# diapers.net
KiCad netlist of a schematic drawn in Altium Designer
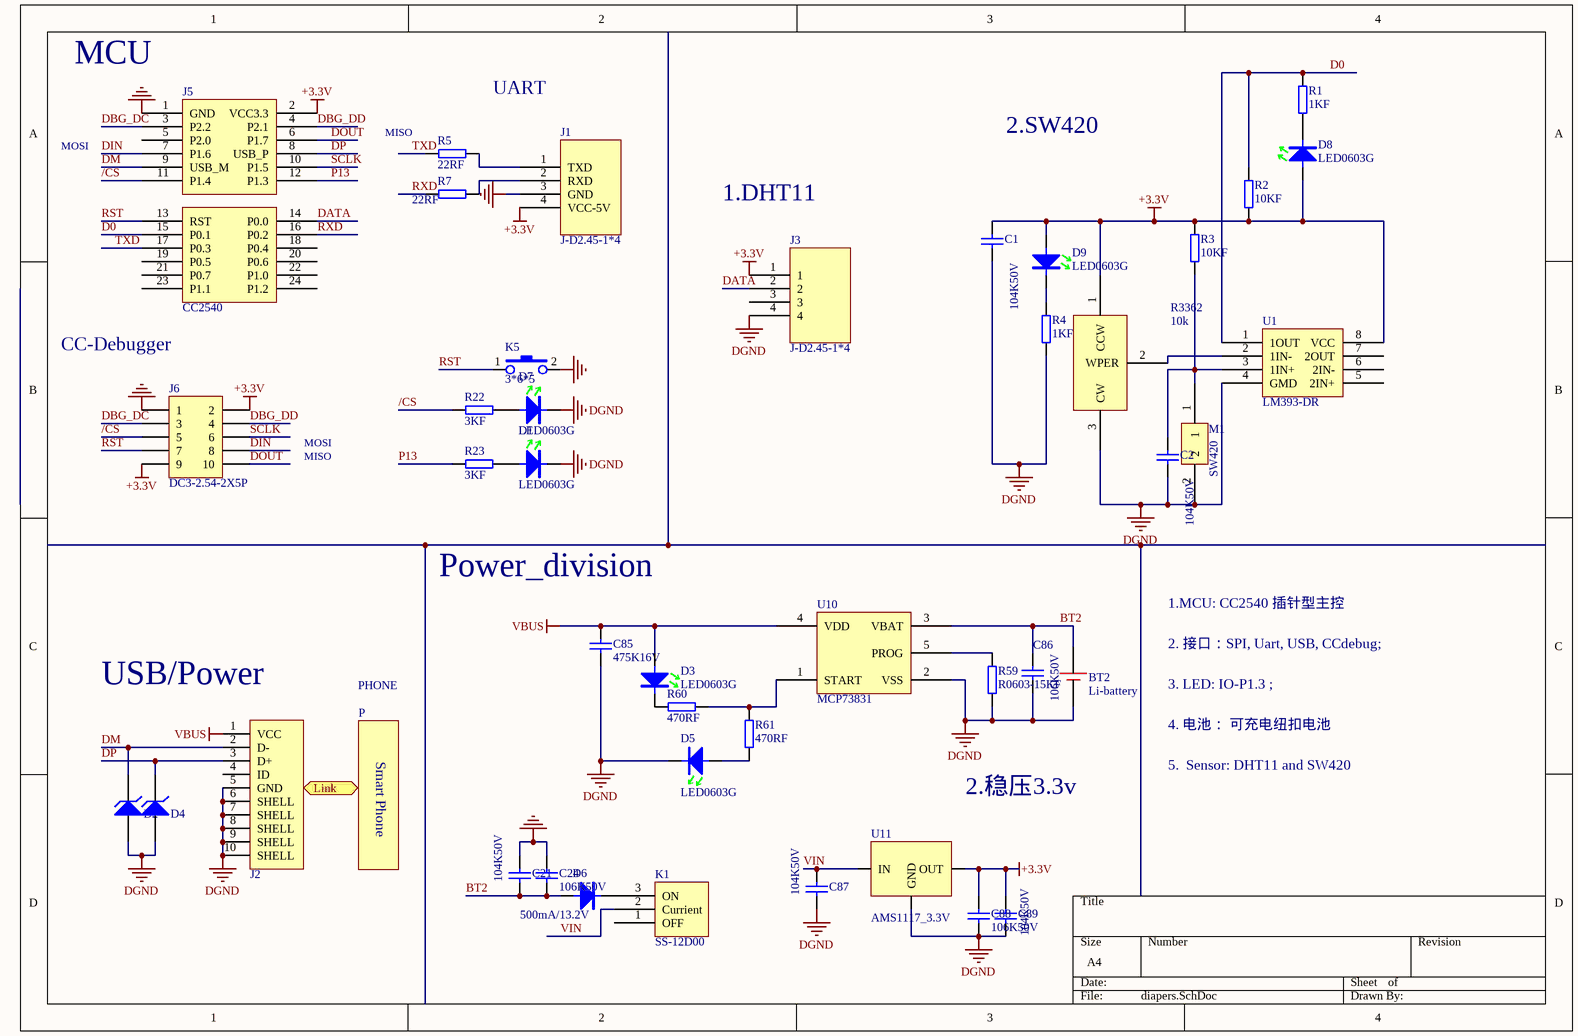
[diagram p0: diapers.SchDoc]

(export (version "E")
  (design (tool "Eeschema 10.0.6"))
  (components
    (comp (ref "BT2")
      (value "Li-battery")
      (footprint "LIR2032")
      (description "纽扣电池LIR2023")
      (libsource (lib "Others") (part "Li-batttery"))
    )
    (comp (ref "C1")
      (value "104K50V")
      (footprint "C0603")
      (description "贴片电容-陶瓷")
      (libsource (lib "Capacitor") (part "C0603X7R-104K50V"))
    )
    (comp (ref "C2")
      (value "104K50V")
      (footprint "C0603")
      (description "贴片电容-陶瓷")
      (libsource (lib "Capacitor") (part "C0603X7R-104K50V"))
    )
    (comp (ref "C21")
      (value "104K50V")
      (footprint "C0603")
      (description "贴片电容-陶瓷")
      (libsource (lib "Capacitor") (part "C0603X7R-104K50V"))
    )
    (comp (ref "C24")
      (value "106K50V")
      (footprint "C0603")
      (description "贴片电容-陶瓷")
      (libsource (lib "Capacitor") (part "C0603X7R-106K50V"))
    )
    (comp (ref "C85")
      (value "475K16V")
      (footprint "C0603")
      (description "贴片电容-陶瓷")
      (libsource (lib "Capacitor") (part "C0603X7R-475K16V"))
    )
    (comp (ref "C86")
      (value "106K50V")
      (footprint "C0603")
      (description "贴片电容-陶瓷")
      (libsource (lib "Capacitor") (part "C0603X7R-106K50V"))
    )
    (comp (ref "C87")
      (value "104K50V")
      (footprint "C0603")
      (description "贴片电容-陶瓷")
      (libsource (lib "Capacitor") (part "C0603X7R-104K50V"))
    )
    (comp (ref "C88")
      (value "106K50V")
      (footprint "C0603")
      (description "贴片电容-陶瓷")
      (libsource (lib "Capacitor") (part "C0603X7R-106K50V"))
    )
    (comp (ref "C89")
      (value "104K50V")
      (footprint "C0603")
      (description "贴片电容-陶瓷")
      (libsource (lib "Capacitor") (part "C0603X7R-104K50V"))
    )
    (comp (ref "D1")
      (value "LED0603G")
      (footprint "D-LED0603G")
      (description "贴片二极管-LED")
      (libsource (lib "aiwacV2.0") (part "DLED-0603-G"))
    )
    (comp (ref "D2")
      (value "ESDA_TR1/0603")
      (footprint "HS_0603D")
      (description "Zener Diode")
      (fields (field (name "PUBLISHER") "*"))
      (libsource (lib "aiwacV2.0") (part "D Zener"))
    )
    (comp (ref "D3")
      (value "LED0603G")
      (footprint "D-LED0603G")
      (description "贴片二极管-LED")
      (libsource (lib "Diode") (part "DLED-0603-G"))
    )
    (comp (ref "D4")
      (value "ESDA_TR1/0603")
      (footprint "HS_0603D")
      (description "Zener Diode")
      (fields (field (name "PUBLISHER") "*"))
      (libsource (lib "aiwacV2.0") (part "D Zener"))
    )
    (comp (ref "D5")
      (value "LED0603G")
      (footprint "D-LED0603G")
      (description "贴片二极管-LED")
      (libsource (lib "Diode") (part "DLED-0603-G"))
    )
    (comp (ref "D6")
      (value "500mA/13.2V")
      (footprint "D1206")
      (description "500mA/13.2V 自恢复保险丝")
      (libsource (lib "Diode") (part "1206MSD"))
    )
    (comp (ref "D7")
      (value "LED0603G")
      (footprint "D-LED0603G")
      (description "贴片二极管-LED")
      (libsource (lib "aiwacV2.0") (part "DLED-0603-G"))
    )
    (comp (ref "D8")
      (value "LED0603G")
      (footprint "D-LED0603G")
      (description "贴片二极管-LED")
      (libsource (lib "Diode") (part "DLED-0603-G"))
    )
    (comp (ref "D9")
      (value "LED0603G")
      (footprint "D-LED0603G")
      (description "贴片二极管-LED")
      (libsource (lib "Diode") (part "DLED-0603-G"))
    )
    (comp (ref "J1")
      (value "J-D2.45-1*4")
      (footprint "D2.54-1*4P")
      (libsource (lib "Connector") (part "J-D2.54-1*4单排排母"))
    )
    (comp (ref "J2")
      (value "USB-MINI-SOCKET")
      (footprint "MICRO-USB - 5.9")
      (description "USB-A卧式插座")
      (libsource (lib "epic2") (part "J-USB-MINI-SOCKET"))
    )
    (comp (ref "J3")
      (value "J-D2.45-1*4")
      (footprint "D2.54-1*4P")
      (libsource (lib "Connector") (part "J-D2.54-1*4单排排母"))
    )
    (comp (ref "J5")
      (value "CC2540")
      (footprint "PCBComponent_1")
      (description "蓝牙主控模块的接口")
      (libsource (lib "Module") (part "CC2540"))
    )
    (comp (ref "J6")
      (value "DC3-2.54-2X5P")
      (footprint "DC3-2.54-2X5P")
      (description "简牛插座-直针")
      (libsource (lib "Connector") (part "J-DC3-2.54-2X5P"))
    )
    (comp (ref "K1")
      (value "SS-12D00")
      (footprint "SS-12D00")
      (libsource (lib "Key") (part "SS-12D00(1P2T) 立式 柄高5MM"))
    )
    (comp (ref "K5")
      (value "3*6*5")
      (footprint "S-K3*6")
      (description "贴片-卧式轻触开关")
      (libsource (lib "Key") (part "3*6*5"))
    )
    (comp (ref "M1")
      (value "SW420")
      (footprint "SW420")
      (description "长闭震动开关")
      (libsource (lib "Module") (part "SW420"))
    )
    (comp (ref "P") (value "PHONE") (libsource (lib "epic") (part "PHONE")))
    (comp (ref "R1")
      (value "1KF")
      (footprint "R0603")
      (description "贴片电阻-通用")
      (libsource (lib "Resistor") (part "R0603-1KF"))
    )
    (comp (ref "R2")
      (value "10KF")
      (footprint "R0603")
      (description "贴片电阻-通用")
      (libsource (lib "Resistor") (part "R0603-10KF"))
    )
    (comp (ref "R3")
      (value "10KF")
      (footprint "R0603")
      (description "贴片电阻-通用")
      (libsource (lib "Resistor") (part "R0603-10KF"))
    )
    (comp (ref "R4")
      (value "1KF")
      (footprint "R0603")
      (description "贴片电阻-通用")
      (libsource (lib "Resistor") (part "R0603-1KF"))
    )
    (comp (ref "R5")
      (value "22RF")
      (footprint "R0603")
      (description "贴片电阻-通用")
      (libsource (lib "Resistor") (part "R0603-22RF"))
    )
    (comp (ref "R7")
      (value "22RF")
      (footprint "R0603")
      (description "贴片电阻-通用")
      (libsource (lib "Resistor") (part "R0603-22RF"))
    )
    (comp (ref "R22")
      (value "3KF")
      (footprint "R0603")
      (description "贴片电阻-通用")
      (libsource (lib "Resistor") (part "R0603-3KF"))
    )
    (comp (ref "R23")
      (value "3KF")
      (footprint "R0603")
      (description "贴片电阻-通用")
      (libsource (lib "Resistor") (part "R0603-3KF"))
    )
    (comp (ref "R59")
      (value "R0603-15KF")
      (footprint "R0603")
      (description "贴片电容-通用")
      (libsource (lib "Resistor") (part "R0603-15KF"))
    )
    (comp (ref "R60")
      (value "470RF")
      (footprint "R0603")
      (description "贴片电阻-通用")
      (libsource (lib "Resistor") (part "R0603-470RF"))
    )
    (comp (ref "R61")
      (value "470RF")
      (footprint "R0603")
      (description "贴片电阻-通用")
      (libsource (lib "Resistor") (part "R0603-470RF"))
    )
    (comp (ref "R3362")
      (value "10k")
      (footprint "R3326P")
      (description "电位器精密可调电阻")
      (libsource (lib "Resistor") (part "R3362-10K"))
    )
    (comp (ref "U1")
      (value "LM393-DR")
      (footprint "LM393")
      (description "双路比较器")
      (libsource (lib "IC") (part "LM393-DR"))
    )
    (comp (ref "U10")
      (value "MCP73831")
      (footprint "SOT23-5N")
      (description "charge IC")
      (libsource (lib "IC") (part "MCP73831"))
    )
    (comp (ref "U11")
      (value "AMS1117_3.3V")
      (footprint "SOT-223")
      (libsource (lib "IC") (part "AMS1117-3.3V"))
    )
  )
  (nets
    (net (code "1") (name "+3.3V") (class "Default")
      (node (ref "C1") (pin "1") (pinfunction "1_1") (pintype "passive"))
      (node (ref "C88") (pin "2") (pinfunction "2_2") (pintype "passive"))
      (node (ref "C89") (pin "1") (pinfunction "1_1") (pintype "passive"))
      (node (ref "D8") (pin "1") (pinfunction "1_1") (pintype "passive"))
      (node (ref "D9") (pin "1") (pinfunction "1_1") (pintype "passive"))
      (node (ref "J1") (pin "4") (pinfunction "VCC-5V_4") (pintype "passive"))
      (node (ref "J3") (pin "1") (pinfunction "TXD_1") (pintype "passive"))
      (node (ref "J5") (pin "2") (pinfunction "VCC3.3_2") (pintype "passive"))
      (node (ref "J6") (pin "2") (pinfunction "2_2") (pintype "passive"))
      (node (ref "J6") (pin "9") (pinfunction "9_9") (pintype "passive"))
      (node (ref "R2") (pin "1") (pinfunction "1_1") (pintype "passive"))
      (node (ref "R3") (pin "2") (pinfunction "2_2") (pintype "passive"))
      (node (ref "R3362") (pin "1") (pinfunction "CCW_1") (pintype "passive"))
      (node (ref "U1") (pin "8") (pinfunction "VCC_8") (pintype "passive"))
      (node (ref "U11") (pin "2") (pinfunction "OUT_2") (pintype "passive"))
    )
    (net (code "2") (name "/BT2") (class "Default")
      (node (ref "BT2") (pin "1") (pinfunction "1_1") (pintype "passive"))
      (node (ref "C21") (pin "2") (pinfunction "2_2") (pintype "passive"))
      (node (ref "C24") (pin "1") (pinfunction "1_1") (pintype "passive"))
      (node (ref "C86") (pin "1") (pinfunction "1_1") (pintype "passive"))
      (node (ref "D6") (pin "1") (pinfunction "1_1") (pintype "passive"))
      (node (ref "U10") (pin "3") (pinfunction "VBAT_3") (pintype "passive"))
    )
    (net (code "3") (name "/D0") (class "Default")
      (node (ref "J5") (pin "15") (pinfunction "P0.1_15") (pintype "passive"))
      (node (ref "R1") (pin "1") (pinfunction "1_1") (pintype "passive"))
      (node (ref "R2") (pin "2") (pinfunction "2_2") (pintype "passive"))
      (node (ref "U1") (pin "1") (pinfunction "1OUT_1") (pintype "passive"))
    )
    (net (code "4") (name "/DATA") (class "Default")
      (node (ref "J3") (pin "2") (pinfunction "RXD_2") (pintype "passive"))
      (node (ref "J5") (pin "14") (pinfunction "P0.0_14") (pintype "passive"))
    )
    (net (code "5") (name "/DBG_DC") (class "Default")
      (node (ref "J5") (pin "3") (pinfunction "P2.2_3") (pintype "passive"))
      (node (ref "J6") (pin "3") (pinfunction "3_3") (pintype "passive"))
    )
    (net (code "6") (name "/DBG_DD") (class "Default")
      (node (ref "J5") (pin "4") (pinfunction "P2.1_4") (pintype "passive"))
      (node (ref "J6") (pin "4") (pinfunction "4_4") (pintype "passive"))
    )
    (net (code "7") (name "/DIN") (class "Default")
      (node (ref "J5") (pin "7") (pinfunction "P1.6_7") (pintype "passive"))
      (node (ref "J6") (pin "8") (pinfunction "8_8") (pintype "passive"))
    )
    (net (code "8") (name "/DM") (class "Default")
      (node (ref "D2") (pin "2") (pinfunction "K_2") (pintype "passive"))
      (node (ref "J2") (pin "2") (pinfunction "D-_2") (pintype "passive"))
      (node (ref "J5") (pin "9") (pinfunction "USB_M_9") (pintype "passive"))
    )
    (net (code "9") (name "/DOUT") (class "Default")
      (node (ref "J5") (pin "6") (pinfunction "P1.7_6") (pintype "passive"))
      (node (ref "J6") (pin "10") (pinfunction "10_10") (pintype "passive"))
    )
    (net (code "10") (name "/DP") (class "Default")
      (node (ref "D4") (pin "2") (pinfunction "K_2") (pintype "passive"))
      (node (ref "J2") (pin "3") (pinfunction "D+_3") (pintype "passive"))
      (node (ref "J5") (pin "8") (pinfunction "USB_P_8") (pintype "passive"))
    )
    (net (code "12") (name "/P13") (class "Default")
      (node (ref "J5") (pin "12") (pinfunction "P1.3_12") (pintype "passive"))
      (node (ref "R23") (pin "1") (pinfunction "1_1") (pintype "passive"))
    )
    (net (code "13") (name "/RST") (class "Default")
      (node (ref "J5") (pin "13") (pinfunction "RST_13") (pintype "passive"))
      (node (ref "J6") (pin "7") (pinfunction "7_7") (pintype "passive"))
      (node (ref "K5") (pin "1") (pinfunction "1_1") (pintype "passive"))
    )
    (net (code "14") (name "/RXD") (class "Default")
      (node (ref "J5") (pin "16") (pinfunction "P0.2_16") (pintype "passive"))
      (node (ref "R7") (pin "2") (pinfunction "2_2") (pintype "passive"))
    )
    (net (code "15") (name "/SCLK") (class "Default")
      (node (ref "J5") (pin "10") (pinfunction "P1.5_10") (pintype "passive"))
      (node (ref "J6") (pin "6") (pinfunction "6_6") (pintype "passive"))
    )
    (net (code "16") (name "/TXD") (class "Default")
      (node (ref "J5") (pin "17") (pinfunction "P0.3_17") (pintype "passive"))
      (node (ref "R5") (pin "2") (pinfunction "2_2") (pintype "passive"))
    )
    (net (code "17") (name "/VIN") (class "Default")
      (node (ref "C87") (pin "1") (pinfunction "1_1") (pintype "passive"))
      (node (ref "K1") (pin "2") (pinfunction "Currient_2") (pintype "passive"))
      (node (ref "U11") (pin "3") (pinfunction "IN_3") (pintype "passive"))
    )
    (net (code "18") (name "/{slash}CS") (class "Default")
      (node (ref "J5") (pin "11") (pinfunction "P1.4_11") (pintype "passive"))
      (node (ref "J6") (pin "5") (pinfunction "5_5") (pintype "passive"))
      (node (ref "R22") (pin "1") (pinfunction "1_1") (pintype "passive"))
    )
    (net (code "19") (name "DGND") (class "Default")
      (node (ref "BT2") (pin "2") (pinfunction "2_2") (pintype "passive"))
      (node (ref "C1") (pin "2") (pinfunction "2_2") (pintype "passive"))
      (node (ref "C2") (pin "2") (pinfunction "2_2") (pintype "passive"))
      (node (ref "C21") (pin "1") (pinfunction "1_1") (pintype "passive"))
      (node (ref "C24") (pin "2") (pinfunction "2_2") (pintype "passive"))
      (node (ref "C85") (pin "2") (pinfunction "2_2") (pintype "passive"))
      (node (ref "C86") (pin "2") (pinfunction "2_2") (pintype "passive"))
      (node (ref "C87") (pin "2") (pinfunction "2_2") (pintype "passive"))
      (node (ref "C88") (pin "1") (pinfunction "1_1") (pintype "passive"))
      (node (ref "C89") (pin "2") (pinfunction "2_2") (pintype "passive"))
      (node (ref "D1") (pin "2") (pinfunction "2_2") (pintype "passive"))
      (node (ref "D2") (pin "1") (pinfunction "A_1") (pintype "passive"))
      (node (ref "D4") (pin "1") (pinfunction "A_1") (pintype "passive"))
      (node (ref "D5") (pin "2") (pinfunction "2_2") (pintype "passive"))
      (node (ref "D7") (pin "2") (pinfunction "2_2") (pintype "passive"))
      (node (ref "J1") (pin "3") (pinfunction "GND_3") (pintype "passive"))
      (node (ref "J2") (pin "10") (pinfunction "SHELL_10") (pintype "passive"))
      (node (ref "J2") (pin "5") (pinfunction "GND_5") (pintype "passive"))
      (node (ref "J2") (pin "6") (pinfunction "SHELL_6") (pintype "passive"))
      (node (ref "J2") (pin "7") (pinfunction "SHELL_7") (pintype "passive"))
      (node (ref "J2") (pin "8") (pinfunction "SHELL_8") (pintype "passive"))
      (node (ref "J2") (pin "9") (pinfunction "SHELL_9") (pintype "passive"))
      (node (ref "J3") (pin "4") (pinfunction "VCC-5V_4") (pintype "passive"))
      (node (ref "J5") (pin "1") (pinfunction "GND_1") (pintype "passive"))
      (node (ref "J6") (pin "1") (pinfunction "1_1") (pintype "passive"))
      (node (ref "K5") (pin "2") (pinfunction "2_2") (pintype "passive"))
      (node (ref "M1") (pin "2") (pinfunction "2_2") (pintype "passive"))
      (node (ref "R3362") (pin "3") (pinfunction "CW_3") (pintype "passive"))
      (node (ref "R4") (pin "1") (pinfunction "1_1") (pintype "passive"))
      (node (ref "R59") (pin "1") (pinfunction "1_1") (pintype "passive"))
      (node (ref "U1") (pin "4") (pinfunction "GMD_4") (pintype "passive"))
      (node (ref "U10") (pin "2") (pinfunction "VSS_2") (pintype "passive"))
      (node (ref "U11") (pin "1") (pinfunction "GND_1") (pintype "passive"))
    )
    (net (code "20") (name "Net-(D1-Pad1)") (class "Default")
      (node (ref "D1") (pin "1") (pinfunction "1_1") (pintype "passive"))
      (node (ref "R23") (pin "2") (pinfunction "2_2") (pintype "passive"))
    )
    (net (code "21") (name "Net-(D3-Pad2)") (class "Default")
      (node (ref "D3") (pin "2") (pinfunction "2_2") (pintype "passive"))
      (node (ref "R60") (pin "1") (pinfunction "1_1") (pintype "passive"))
    )
    (net (code "22") (name "Net-(D5-Pad1)") (class "Default")
      (node (ref "D5") (pin "1") (pinfunction "1_1") (pintype "passive"))
      (node (ref "R61") (pin "1") (pinfunction "1_1") (pintype "passive"))
    )
    (net (code "23") (name "Net-(D7-Pad1)") (class "Default")
      (node (ref "D7") (pin "1") (pinfunction "1_1") (pintype "passive"))
      (node (ref "R22") (pin "2") (pinfunction "2_2") (pintype "passive"))
    )
    (net (code "24") (name "Net-(D8-Pad2)") (class "Default")
      (node (ref "D8") (pin "2") (pinfunction "2_2") (pintype "passive"))
      (node (ref "R1") (pin "2") (pinfunction "2_2") (pintype "passive"))
    )
    (net (code "25") (name "Net-(D9-Pad2)") (class "Default")
      (node (ref "D9") (pin "2") (pinfunction "2_2") (pintype "passive"))
      (node (ref "R4") (pin "2") (pinfunction "2_2") (pintype "passive"))
    )
    (net (code "26") (name "Net-(J1-RXD)") (class "Default")
      (node (ref "J1") (pin "2") (pinfunction "RXD_2") (pintype "passive"))
      (node (ref "R7") (pin "1") (pinfunction "1_1") (pintype "passive"))
    )
    (net (code "27") (name "Net-(J1-TXD)") (class "Default")
      (node (ref "J1") (pin "1") (pinfunction "TXD_1") (pintype "passive"))
      (node (ref "R5") (pin "1") (pinfunction "1_1") (pintype "passive"))
    )
    (net (code "28") (name "Net-(K1-ON)") (class "Default")
      (node (ref "D6") (pin "2") (pinfunction "2_2") (pintype "passive"))
      (node (ref "K1") (pin "3") (pinfunction "ON_3") (pintype "passive"))
    )
    (net (code "29") (name "Net-(R3362-WPER)") (class "Default")
      (node (ref "R3362") (pin "2") (pinfunction "WPER_2") (pintype "passive"))
      (node (ref "U1") (pin "2") (pinfunction "1IN-_2") (pintype "passive"))
    )
    (net (code "30") (name "Net-(U1-1IN+)") (class "Default")
      (node (ref "C2") (pin "1") (pinfunction "1_1") (pintype "passive"))
      (node (ref "M1") (pin "1") (pinfunction "1_1") (pintype "passive"))
      (node (ref "R3") (pin "1") (pinfunction "1_1") (pintype "passive"))
      (node (ref "U1") (pin "3") (pinfunction "1IN+_3") (pintype "passive"))
    )
    (net (code "31") (name "Net-(U10-PROG)") (class "Default")
      (node (ref "R59") (pin "2") (pinfunction "2_2") (pintype "passive"))
      (node (ref "U10") (pin "5") (pinfunction "PROG_5") (pintype "passive"))
    )
    (net (code "32") (name "Net-(U10-START)") (class "Default")
      (node (ref "R60") (pin "2") (pinfunction "2_2") (pintype "passive"))
      (node (ref "R61") (pin "2") (pinfunction "2_2") (pintype "passive"))
      (node (ref "U10") (pin "1") (pinfunction "START_1") (pintype "passive"))
    )
    (net (code "33") (name "VBUS") (class "Default")
      (node (ref "C85") (pin "1") (pinfunction "1_1") (pintype "passive"))
      (node (ref "D3") (pin "1") (pinfunction "1_1") (pintype "passive"))
      (node (ref "J2") (pin "1") (pinfunction "VCC_1") (pintype "passive"))
      (node (ref "U10") (pin "4") (pinfunction "VDD_4") (pintype "passive"))
    )
    (net (code "34") (name "unconnected-(J2-ID-Pad4)") (class "Default")
      (node (ref "J2") (pin "4") (pinfunction "ID_4") (pintype "passive"))
    )
    (net (code "35") (name "unconnected-(J3-GND-Pad3)") (class "Default")
      (node (ref "J3") (pin "3") (pinfunction "GND_3") (pintype "passive"))
    )
    (net (code "36") (name "unconnected-(J5-P0.4-Pad18)") (class "Default")
      (node (ref "J5") (pin "18") (pinfunction "P0.4_18") (pintype "passive"))
    )
    (net (code "37") (name "unconnected-(J5-P0.5-Pad19)") (class "Default")
      (node (ref "J5") (pin "19") (pinfunction "P0.5_19") (pintype "passive"))
    )
    (net (code "38") (name "unconnected-(J5-P0.6-Pad20)") (class "Default")
      (node (ref "J5") (pin "20") (pinfunction "P0.6_20") (pintype "passive"))
    )
    (net (code "39") (name "unconnected-(J5-P0.7-Pad21)") (class "Default")
      (node (ref "J5") (pin "21") (pinfunction "P0.7_21") (pintype "passive"))
    )
    (net (code "40") (name "unconnected-(J5-P1.0-Pad22)") (class "Default")
      (node (ref "J5") (pin "22") (pinfunction "P1.0_22") (pintype "passive"))
    )
    (net (code "41") (name "unconnected-(J5-P1.1-Pad23)") (class "Default")
      (node (ref "J5") (pin "23") (pinfunction "P1.1_23") (pintype "passive"))
    )
    (net (code "42") (name "unconnected-(J5-P1.2-Pad24)") (class "Default")
      (node (ref "J5") (pin "24") (pinfunction "P1.2_24") (pintype "passive"))
    )
    (net (code "43") (name "unconnected-(J5-P2.0-Pad5)") (class "Default")
      (node (ref "J5") (pin "5") (pinfunction "P2.0_5") (pintype "passive"))
    )
    (net (code "44") (name "unconnected-(K1-OFF-Pad1)") (class "Default")
      (node (ref "K1") (pin "1") (pinfunction "OFF_1") (pintype "passive"))
    )
    (net (code "45") (name "unconnected-(U1-2IN+-Pad5)") (class "Default")
      (node (ref "U1") (pin "5") (pinfunction "2IN+_5") (pintype "passive"))
    )
    (net (code "46") (name "unconnected-(U1-2IN--Pad6)") (class "Default")
      (node (ref "U1") (pin "6") (pinfunction "2IN-_6") (pintype "passive"))
    )
    (net (code "47") (name "unconnected-(U1-2OUT-Pad7)") (class "Default")
      (node (ref "U1") (pin "7") (pinfunction "2OUT_7") (pintype "passive"))
    )
  )
)
